# HW_HDSP2072.net
KiCad netlist of a schematic drawn in Altium Designer
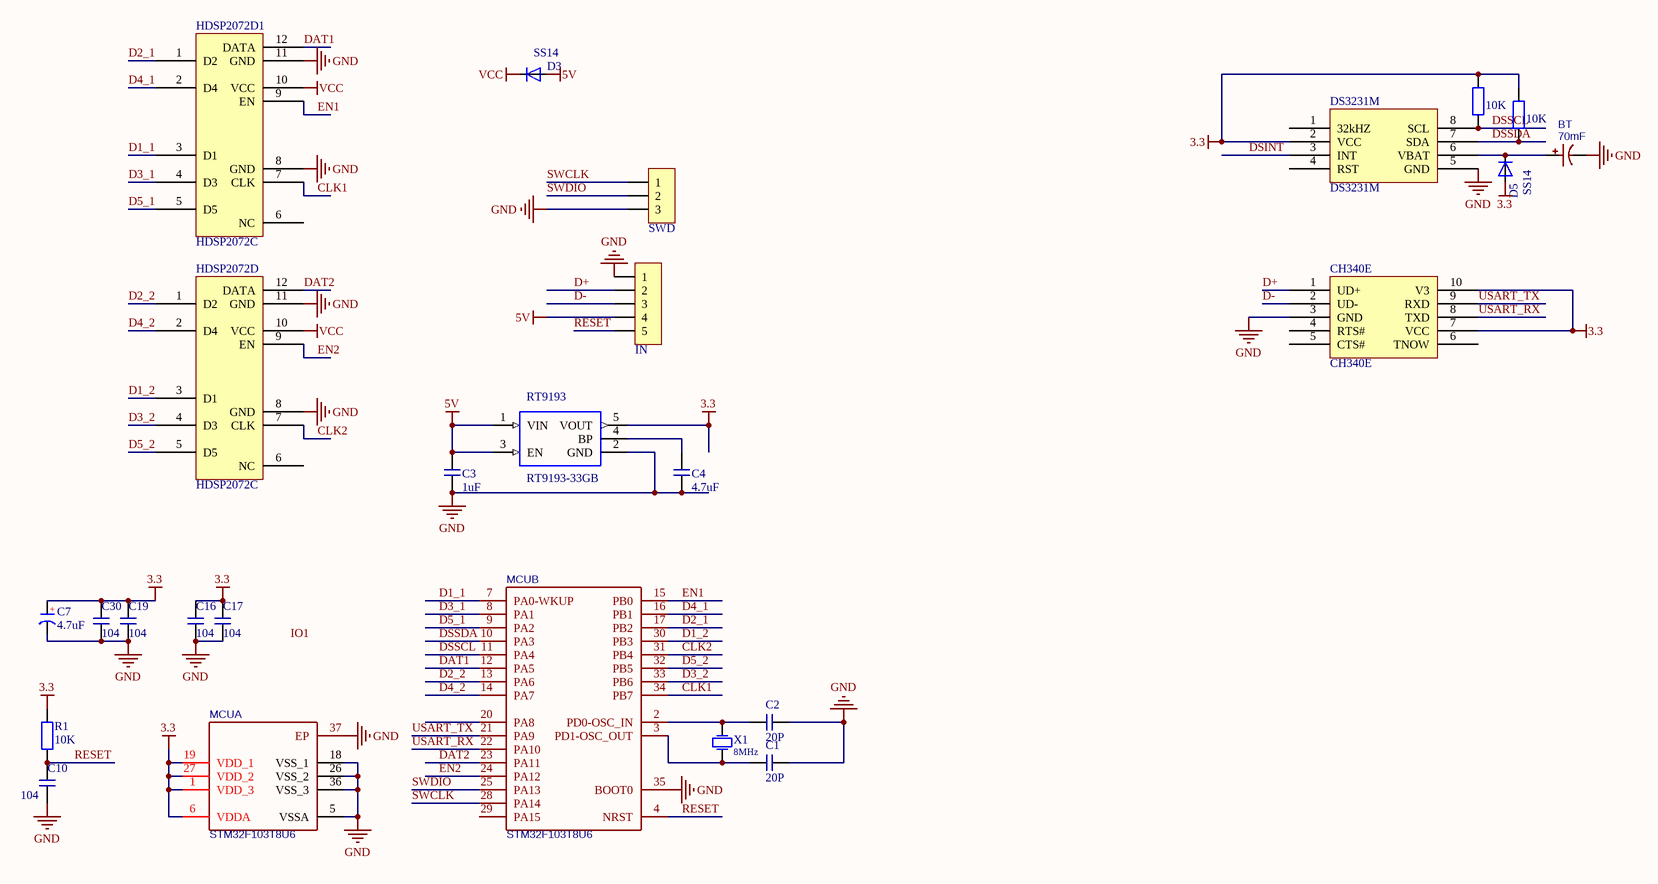
[diagram p0: HW_HDSP2072.SchDoc]

(export (version "E")
  (design (tool "Eeschema 10.0.6"))
  (components
    (comp (ref "BT")
      (value "70mF")
      (footprint "CAP-TH_BD4.8-P3.95_SM3R3703T01")
      (fields
        (field (name "BOM_SUPPLIER PART") "C132600")
        (field (name "BOM_MANUFACTURER PART") "SM3R3703T01")
        (field (name "CONTRIBUTOR") "LCSC")
      )
      (libsource (lib "altium-import") (part "root_0_70mF_"))
    )
    (comp (ref "C1") (value "20P") (footprint "0603C") (libsource (lib "Schlib1") (part "电容")))
    (comp (ref "C2") (value "20P") (footprint "0603C") (libsource (lib "Schlib1") (part "电容")))
    (comp (ref "C3") (value "1uF") (footprint "0603C") (libsource (lib "Schlib1") (part "电容")))
    (comp (ref "C4") (value "4.7uF") (footprint "0603C") (libsource (lib "Schlib1") (part "电容")))
    (comp (ref "C7")
      (value "4.7uF")
      (footprint "3528-B-TA")
      (description "贴片钽电容")
      (libsource (lib "3.1   - 电阻-电容-电感") (part "C-CD"))
    )
    (comp (ref "C10") (value "104") (footprint "0603C") (libsource (lib "Schlib1") (part "电容")))
    (comp (ref "C16") (value "104") (footprint "0603C") (libsource (lib "Schlib1") (part "电容")))
    (comp (ref "C17") (value "104") (footprint "0603C") (libsource (lib "Schlib1") (part "电容")))
    (comp (ref "C19") (value "104") (footprint "0603C") (libsource (lib "Schlib1") (part "电容")))
    (comp (ref "C30") (value "104") (footprint "0603C") (libsource (lib "Schlib1") (part "电容")))
    (comp (ref "CH340E") (value "CH340E") (footprint "MSOP10_L") (libsource (lib "CUBE_T1") (part "CH340E")))
    (comp (ref "D3")
      (value "SS14")
      (footprint "SOD323_1N4148WS")
      (description "Diode Switching 75V 0.3A 2-Pin SOD-323 T/R")
      (fields (field (name "MF") "ON Semiconductor") (field (name "MP") "1N4148WS"))
      (libsource (lib "1N4148WS") (part "1N4148WS"))
    )
    (comp (ref "D5")
      (value "SS14")
      (footprint "SOD323_1N4148WS")
      (description "Diode Switching 75V 0.3A 2-Pin SOD-323 T/R")
      (fields (field (name "MF") "ON Semiconductor") (field (name "MP") "1N4148WS"))
      (libsource (lib "1N4148WS") (part "1N4148WS"))
    )
    (comp (ref "DS3231M") (value "DS3231M") (footprint "SOP8") (libsource (lib "CUBE_T1") (part "DS3231M")))
    (comp (ref "HDSP2072D")
      (value "HDSP2072C")
      (footprint "HDSP2072SH")
      (libsource (lib "HDSP2072") (part "HDSP2072"))
    )
    (comp (ref "HDSP2072D1")
      (value "HDSP2072C")
      (footprint "HDSP2072SH")
      (libsource (lib "HDSP2072") (part "HDSP2072"))
    )
    (comp (ref "IN")
      (value "HDR-1X5")
      (footprint "ZH1.5-LS-5P")
      (description "5P接插件")
      (libsource (lib "4.3   - 接插件-脚距1.5") (part "Header 5"))
    )
    (comp (ref "MCU")
      (value "STM32F103T8U6")
      (footprint "VFQFPN36_L6.0-W6.0-P0.50-BL-EP3.7")
      (fields (field (name "BOM_SUPPLIER PART") "C19671") (field (name "SUBPART_NO") "2"))
      (libsource (lib "HDSP2072") (part "STM32F103T8U6"))
    )
    (comp (ref "R1")
      (value "10K")
      (footprint "0603R")
      (description "贴片电阻")
      (libsource (lib "3.1   - 电阻-电容-电感") (part "R"))
    )
    (comp (ref "R4")
      (value "10K")
      (footprint "0603R")
      (description "贴片电阻")
      (libsource (lib "3.1   - 电阻-电容-电感") (part "R"))
    )
    (comp (ref "R10")
      (value "10K")
      (footprint "0603R")
      (description "贴片电阻")
      (libsource (lib "3.1   - 电阻-电容-电感") (part "R"))
    )
    (comp (ref "RT9193")
      (value "RT9193-33GB")
      (footprint "sot23-5")
      (description "RT9193 Series 300 mA 3.3 V Ultra-Low Noise Ultra-Fast CMOS LDO Regulator-SC-70-5")
      (fields (field (name "MF") "Richtek USA"))
      (libsource (lib "RT9193-33GB") (part "RT9193-33GB"))
    )
    (comp (ref "SWD")
      (value "HDR-1X3")
      (footprint "ZH1.5-LS-3P")
      (description "3P接插件")
      (libsource (lib "4.3   - 接插件-脚距1.5") (part "Header 3"))
    )
    (comp (ref "X1")
      (value "8MHz")
      (footprint "OSC 5032-2P")
      (description "XTAL,8MHz,±20PPM,12.6*4.5")
      (fields (field (name "Comment") "1.6.1.01.005.001"))
      (libsource (lib "Mark_7") (part "1.6.1.01.005.001"))
    )
  )
  (nets
    (net (code "1") (name "/CLK1") (class "Default")
      (node (ref "HDSP2072D1") (pin "7") (pinfunction "CLK_7") (pintype "passive"))
      (node (ref "MCU") (pin "34") (pinfunction "PB7_34") (pintype "passive"))
    )
    (net (code "2") (name "/CLK2") (class "Default")
      (node (ref "HDSP2072D") (pin "7") (pinfunction "CLK_7") (pintype "passive"))
      (node (ref "MCU") (pin "31") (pinfunction "PB4_31") (pintype "passive"))
    )
    (net (code "3") (name "/D+") (class "Default")
      (node (ref "CH340E") (pin "1") (pinfunction "UD+_1") (pintype "passive"))
      (node (ref "IN") (pin "2") (pinfunction "2_2") (pintype "passive"))
    )
    (net (code "4") (name "/D-") (class "Default")
      (node (ref "CH340E") (pin "2") (pinfunction "UD-_2") (pintype "passive"))
      (node (ref "IN") (pin "3") (pinfunction "3_3") (pintype "passive"))
    )
    (net (code "5") (name "/D1_1") (class "Default")
      (node (ref "HDSP2072D1") (pin "3") (pinfunction "D1_3") (pintype "passive"))
      (node (ref "MCU") (pin "7") (pinfunction "PA0-WKUP_7") (pintype "passive"))
    )
    (net (code "6") (name "/D1_2") (class "Default")
      (node (ref "HDSP2072D") (pin "3") (pinfunction "D1_3") (pintype "passive"))
      (node (ref "MCU") (pin "30") (pinfunction "PB3_30") (pintype "passive"))
    )
    (net (code "7") (name "/D2_1") (class "Default")
      (node (ref "HDSP2072D1") (pin "1") (pinfunction "D2_1") (pintype "passive"))
      (node (ref "MCU") (pin "17") (pinfunction "PB2_17") (pintype "passive"))
    )
    (net (code "8") (name "/D2_2") (class "Default")
      (node (ref "HDSP2072D") (pin "1") (pinfunction "D2_1") (pintype "passive"))
      (node (ref "MCU") (pin "13") (pinfunction "PA6_13") (pintype "passive"))
    )
    (net (code "9") (name "/D3_1") (class "Default")
      (node (ref "HDSP2072D1") (pin "4") (pinfunction "D3_4") (pintype "passive"))
      (node (ref "MCU") (pin "8") (pinfunction "PA1_8") (pintype "passive"))
    )
    (net (code "10") (name "/D3_2") (class "Default")
      (node (ref "HDSP2072D") (pin "4") (pinfunction "D3_4") (pintype "passive"))
      (node (ref "MCU") (pin "33") (pinfunction "PB6_33") (pintype "passive"))
    )
    (net (code "11") (name "/D4_1") (class "Default")
      (node (ref "HDSP2072D1") (pin "2") (pinfunction "D4_2") (pintype "passive"))
      (node (ref "MCU") (pin "16") (pinfunction "PB1_16") (pintype "passive"))
    )
    (net (code "12") (name "/D4_2") (class "Default")
      (node (ref "HDSP2072D") (pin "2") (pinfunction "D4_2") (pintype "passive"))
      (node (ref "MCU") (pin "14") (pinfunction "PA7_14") (pintype "passive"))
    )
    (net (code "13") (name "/D5_1") (class "Default")
      (node (ref "HDSP2072D1") (pin "5") (pinfunction "D5_5") (pintype "passive"))
      (node (ref "MCU") (pin "9") (pinfunction "PA2_9") (pintype "passive"))
    )
    (net (code "14") (name "/D5_2") (class "Default")
      (node (ref "HDSP2072D") (pin "5") (pinfunction "D5_5") (pintype "passive"))
      (node (ref "MCU") (pin "32") (pinfunction "PB5_32") (pintype "passive"))
    )
    (net (code "15") (name "/DAT1") (class "Default")
      (node (ref "HDSP2072D1") (pin "12") (pinfunction "DATA_12") (pintype "passive"))
      (node (ref "MCU") (pin "12") (pinfunction "PA5_12") (pintype "passive"))
    )
    (net (code "16") (name "/DAT2") (class "Default")
      (node (ref "HDSP2072D") (pin "12") (pinfunction "DATA_12") (pintype "passive"))
      (node (ref "MCU") (pin "23") (pinfunction "PA11_23") (pintype "passive"))
    )
    (net (code "17") (name "/DSINT") (class "Default")
      (node (ref "DS3231M") (pin "3") (pinfunction "INT_3") (pintype "passive"))
    )
    (net (code "18") (name "/DSSCL") (class "Default")
      (node (ref "DS3231M") (pin "8") (pinfunction "SCL_8") (pintype "passive"))
      (node (ref "MCU") (pin "11") (pinfunction "PA4_11") (pintype "passive"))
      (node (ref "R10") (pin "2") (pinfunction "2_2") (pintype "passive"))
    )
    (net (code "19") (name "/DSSDA") (class "Default")
      (node (ref "DS3231M") (pin "7") (pinfunction "SDA_7") (pintype "passive"))
      (node (ref "MCU") (pin "10") (pinfunction "PA3_10") (pintype "passive"))
      (node (ref "R4") (pin "2") (pinfunction "2_2") (pintype "passive"))
    )
    (net (code "20") (name "/EN1") (class "Default")
      (node (ref "HDSP2072D1") (pin "9") (pinfunction "EN_9") (pintype "passive"))
      (node (ref "MCU") (pin "15") (pinfunction "PB0_15") (pintype "passive"))
    )
    (net (code "21") (name "/EN2") (class "Default")
      (node (ref "HDSP2072D") (pin "9") (pinfunction "EN_9") (pintype "passive"))
      (node (ref "MCU") (pin "24") (pinfunction "PA12_24") (pintype "passive"))
    )
    (net (code "23") (name "/RESET") (class "Default")
      (node (ref "C10") (pin "1") (pinfunction "1_1") (pintype "passive"))
      (node (ref "IN") (pin "5") (pinfunction "5_5") (pintype "passive"))
      (node (ref "MCU") (pin "4") (pinfunction "NRST_4") (pintype "passive"))
      (node (ref "R1") (pin "2") (pinfunction "2_2") (pintype "passive"))
    )
    (net (code "24") (name "/SWCLK") (class "Default")
      (node (ref "MCU") (pin "28") (pinfunction "PA14_28") (pintype "passive"))
      (node (ref "SWD") (pin "1") (pinfunction "1_1") (pintype "passive"))
    )
    (net (code "25") (name "/SWDIO") (class "Default")
      (node (ref "MCU") (pin "25") (pinfunction "PA13_25") (pintype "passive"))
      (node (ref "SWD") (pin "2") (pinfunction "2_2") (pintype "passive"))
    )
    (net (code "26") (name "/USART_RX") (class "Default")
      (node (ref "CH340E") (pin "8") (pinfunction "TXD_8") (pintype "passive"))
      (node (ref "MCU") (pin "22") (pinfunction "PA10_22") (pintype "passive"))
    )
    (net (code "27") (name "/USART_TX") (class "Default")
      (node (ref "CH340E") (pin "9") (pinfunction "RXD_9") (pintype "passive"))
      (node (ref "MCU") (pin "21") (pinfunction "PA9_21") (pintype "passive"))
    )
    (net (code "28") (name "3.3") (class "Default")
      (node (ref "C16") (pin "1") (pinfunction "1_1") (pintype "passive"))
      (node (ref "C17") (pin "1") (pinfunction "1_1") (pintype "passive"))
      (node (ref "C19") (pin "1") (pinfunction "1_1") (pintype "passive"))
      (node (ref "C30") (pin "1") (pinfunction "1_1") (pintype "passive"))
      (node (ref "C7") (pin "1") (pinfunction "A_1") (pintype "passive"))
      (node (ref "CH340E") (pin "10") (pinfunction "V3_10") (pintype "passive"))
      (node (ref "CH340E") (pin "7") (pinfunction "VCC_7") (pintype "passive"))
      (node (ref "D5") (pin "A") (pinfunction "A_A") (pintype "passive"))
      (node (ref "DS3231M") (pin "2") (pinfunction "VCC_2") (pintype "passive"))
      (node (ref "MCU") (pin "1") (pinfunction "VDD_3_1") (pintype "passive"))
      (node (ref "MCU") (pin "19") (pinfunction "VDD_1_19") (pintype "passive"))
      (node (ref "MCU") (pin "27") (pinfunction "VDD_2_27") (pintype "passive"))
      (node (ref "MCU") (pin "6") (pinfunction "VDDA_6") (pintype "passive"))
      (node (ref "R1") (pin "1") (pinfunction "1_1") (pintype "passive"))
      (node (ref "R10") (pin "1") (pinfunction "1_1") (pintype "passive"))
      (node (ref "R4") (pin "1") (pinfunction "1_1") (pintype "passive"))
      (node (ref "RT9193") (pin "5") (pinfunction "VOUT_5") (pintype "output"))
    )
    (net (code "29") (name "5V") (class "Default")
      (node (ref "C3") (pin "2") (pinfunction "2_2") (pintype "passive"))
      (node (ref "D3") (pin "A") (pinfunction "A_A") (pintype "passive"))
      (node (ref "IN") (pin "4") (pinfunction "4_4") (pintype "passive"))
      (node (ref "RT9193") (pin "1") (pinfunction "VIN_1") (pintype "input"))
      (node (ref "RT9193") (pin "3") (pinfunction "EN_3") (pintype "input"))
    )
    (net (code "30") (name "GND") (class "Default")
      (node (ref "BT") (pin "2") (pinfunction "2_2") (pintype "passive"))
      (node (ref "C1") (pin "1") (pinfunction "1_1") (pintype "passive"))
      (node (ref "C10") (pin "2") (pinfunction "2_2") (pintype "passive"))
      (node (ref "C16") (pin "2") (pinfunction "2_2") (pintype "passive"))
      (node (ref "C17") (pin "2") (pinfunction "2_2") (pintype "passive"))
      (node (ref "C19") (pin "2") (pinfunction "2_2") (pintype "passive"))
      (node (ref "C2") (pin "1") (pinfunction "1_1") (pintype "passive"))
      (node (ref "C3") (pin "1") (pinfunction "1_1") (pintype "passive"))
      (node (ref "C30") (pin "2") (pinfunction "2_2") (pintype "passive"))
      (node (ref "C4") (pin "1") (pinfunction "1_1") (pintype "passive"))
      (node (ref "C7") (pin "2") (pinfunction "K_2") (pintype "passive"))
      (node (ref "CH340E") (pin "3") (pinfunction "GND_3") (pintype "passive"))
      (node (ref "DS3231M") (pin "5") (pinfunction "GND_5") (pintype "passive"))
      (node (ref "HDSP2072D") (pin "11") (pinfunction "GND_11") (pintype "passive"))
      (node (ref "HDSP2072D") (pin "8") (pinfunction "GND_8") (pintype "passive"))
      (node (ref "HDSP2072D1") (pin "11") (pinfunction "GND_11") (pintype "passive"))
      (node (ref "HDSP2072D1") (pin "8") (pinfunction "GND_8") (pintype "passive"))
      (node (ref "IN") (pin "1") (pinfunction "1_1") (pintype "passive"))
      (node (ref "MCU") (pin "18") (pinfunction "VSS_1_18") (pintype "passive"))
      (node (ref "MCU") (pin "26") (pinfunction "VSS_2_26") (pintype "passive"))
      (node (ref "MCU") (pin "35") (pinfunction "BOOT0_35") (pintype "passive"))
      (node (ref "MCU") (pin "36") (pinfunction "VSS_3_36") (pintype "passive"))
      (node (ref "MCU") (pin "37") (pinfunction "EP_37") (pintype "passive"))
      (node (ref "MCU") (pin "5") (pinfunction "VSSA_5") (pintype "passive"))
      (node (ref "RT9193") (pin "2") (pinfunction "GND_2") (pintype "power_in"))
      (node (ref "SWD") (pin "3") (pinfunction "3_3") (pintype "passive"))
    )
    (net (code "31") (name "Net-(DS3231M-VBAT)") (class "Default")
      (node (ref "BT") (pin "1") (pinfunction "1_1") (pintype "passive"))
      (node (ref "D5") (pin "C") (pinfunction "C_C") (pintype "passive"))
      (node (ref "DS3231M") (pin "6") (pinfunction "VBAT_6") (pintype "passive"))
    )
    (net (code "32") (name "Net-(MCUB-PD0-OSC_IN)") (class "Default")
      (node (ref "C2") (pin "2") (pinfunction "2_2") (pintype "passive"))
      (node (ref "MCU") (pin "2") (pinfunction "PD0-OSC_IN_2") (pintype "passive"))
      (node (ref "X1") (pin "1") (pinfunction "OSC1_1") (pintype "passive"))
    )
    (net (code "33") (name "Net-(MCUB-PD1-OSC_OUT)") (class "Default")
      (node (ref "C1") (pin "2") (pinfunction "2_2") (pintype "passive"))
      (node (ref "MCU") (pin "3") (pinfunction "PD1-OSC_OUT_3") (pintype "passive"))
      (node (ref "X1") (pin "2") (pinfunction "OSC2_2") (pintype "passive"))
    )
    (net (code "34") (name "Net-(RT9193-BP)") (class "Default")
      (node (ref "C4") (pin "2") (pinfunction "2_2") (pintype "passive"))
      (node (ref "RT9193") (pin "4") (pinfunction "BP_4") (pintype "passive"))
    )
    (net (code "35") (name "VCC") (class "Default")
      (node (ref "D3") (pin "C") (pinfunction "C_C") (pintype "passive"))
      (node (ref "HDSP2072D") (pin "10") (pinfunction "VCC_10") (pintype "passive"))
      (node (ref "HDSP2072D1") (pin "10") (pinfunction "VCC_10") (pintype "passive"))
    )
    (net (code "36") (name "unconnected-(CH340E-CTS#-Pad5)") (class "Default")
      (node (ref "CH340E") (pin "5") (pinfunction "CTS#_5") (pintype "passive"))
    )
    (net (code "37") (name "unconnected-(CH340E-RTS#-Pad4)") (class "Default")
      (node (ref "CH340E") (pin "4") (pinfunction "RTS#_4") (pintype "passive"))
    )
    (net (code "38") (name "unconnected-(CH340E-TNOW-Pad6)") (class "Default")
      (node (ref "CH340E") (pin "6") (pinfunction "TNOW_6") (pintype "passive"))
    )
    (net (code "39") (name "unconnected-(DS3231M-32kHZ-Pad1)") (class "Default")
      (node (ref "DS3231M") (pin "1") (pinfunction "32kHZ_1") (pintype "passive"))
    )
    (net (code "40") (name "unconnected-(DS3231M-RST-Pad4)") (class "Default")
      (node (ref "DS3231M") (pin "4") (pinfunction "RST_4") (pintype "passive"))
    )
    (net (code "41") (name "unconnected-(HDSP2072D-NC-Pad6)") (class "Default")
      (node (ref "HDSP2072D") (pin "6") (pinfunction "NC_6") (pintype "passive"))
    )
    (net (code "42") (name "unconnected-(HDSP2072D1-NC-Pad6)") (class "Default")
      (node (ref "HDSP2072D1") (pin "6") (pinfunction "NC_6") (pintype "passive"))
    )
    (net (code "43") (name "unconnected-(MCUB-PA8-Pad20)") (class "Default")
      (node (ref "MCU") (pin "20") (pinfunction "PA8_20") (pintype "passive"))
    )
    (net (code "44") (name "unconnected-(MCUB-PA15-Pad29)") (class "Default")
      (node (ref "MCU") (pin "29") (pinfunction "PA15_29") (pintype "passive"))
    )
  )
)
